# WirelessChargerTx.net
KiCad netlist of a schematic drawn in Altium Designer
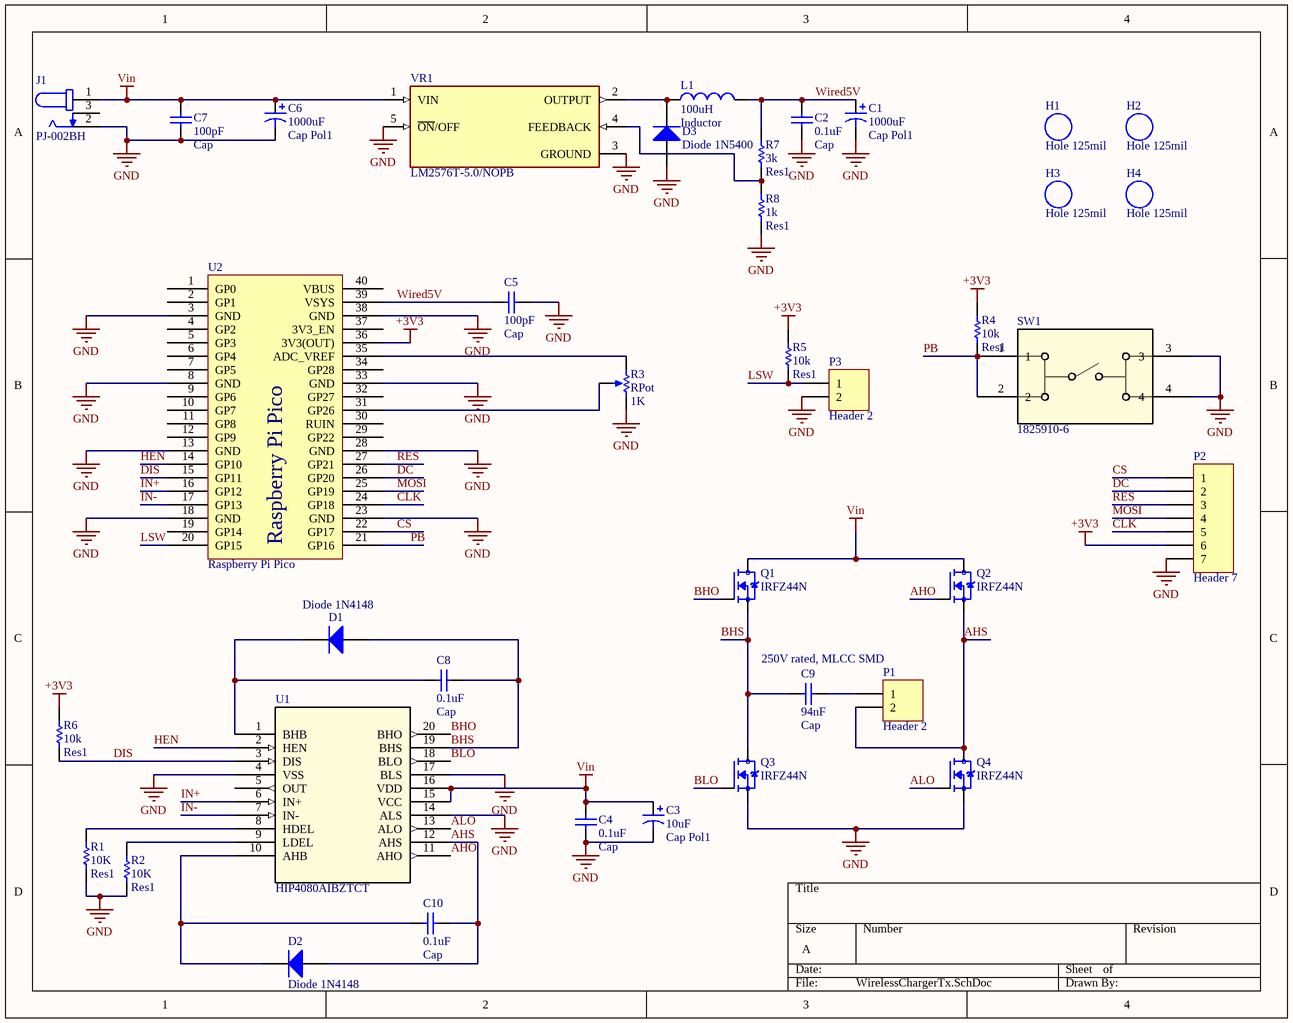
[diagram p0: WirelessChargerTx.SchDoc]

(export (version "E")
  (design (tool "Eeschema 10.0.6"))
  (components
    (comp (ref "C1")
      (value "Cap Pol1")
      (footprint "RB7.6-15")
      (description "Polarized Capacitor (Radial)")
      (fields (field (name "ALTIUM_VALUE") "1000uF") (field (name "PUBLISHER") "Altium Limited"))
      (libsource (lib "Miscellaneous Devices") (part "Cap Pol1"))
    )
    (comp (ref "C2")
      (value "Cap")
      (footprint "RAD-0.3")
      (description "Capacitor")
      (fields (field (name "ALTIUM_VALUE") "0.1uF") (field (name "PUBLISHER") "Altium Limited"))
      (libsource (lib "Miscellaneous Devices") (part "Cap"))
    )
    (comp (ref "C3")
      (value "Cap Pol1")
      (footprint "CAP_10uF")
      (description "Polarized Capacitor (Radial)")
      (fields (field (name "ALTIUM_VALUE") "10uF") (field (name "PUBLISHER") "Altium Limited"))
      (libsource (lib "Miscellaneous Devices") (part "Cap Pol1"))
    )
    (comp (ref "C4")
      (value "Cap")
      (footprint "c0805")
      (description "Capacitor")
      (fields (field (name "ALTIUM_VALUE") "0.1uF") (field (name "PUBLISHER") "Altium Limited"))
      (libsource (lib "Miscellaneous Devices") (part "Cap"))
    )
    (comp (ref "C5")
      (value "Cap")
      (footprint "RAD-0.3")
      (description "Capacitor")
      (fields (field (name "ALTIUM_VALUE") "100pF") (field (name "PUBLISHER") "Altium Limited"))
      (libsource (lib "Miscellaneous Devices") (part "Cap"))
    )
    (comp (ref "C6")
      (value "Cap Pol1")
      (footprint "RB7.6-15")
      (description "Polarized Capacitor (Radial)")
      (fields (field (name "ALTIUM_VALUE") "1000uF") (field (name "PUBLISHER") "Altium Limited"))
      (libsource (lib "Miscellaneous Devices") (part "Cap Pol1"))
    )
    (comp (ref "C7")
      (value "Cap")
      (footprint "RAD-0.3")
      (description "Capacitor")
      (fields (field (name "ALTIUM_VALUE") "100pF") (field (name "PUBLISHER") "Altium Limited"))
      (libsource (lib "Miscellaneous Devices") (part "Cap"))
    )
    (comp (ref "C8")
      (value "Cap")
      (footprint "C0805")
      (description "Capacitor")
      (fields (field (name "ALTIUM_VALUE") "0.1uF") (field (name "PUBLISHER") "Altium Limited"))
      (libsource (lib "Miscellaneous Devices") (part "Cap"))
    )
    (comp (ref "C9")
      (value "Cap")
      (footprint "C1210")
      (description "Capacitor")
      (fields (field (name "ALTIUM_VALUE") "94nF") (field (name "PUBLISHER") "Altium Limited"))
      (libsource (lib "Miscellaneous Devices") (part "Cap"))
    )
    (comp (ref "C10")
      (value "Cap")
      (footprint "C0805")
      (description "Capacitor")
      (fields (field (name "ALTIUM_VALUE") "0.1uF") (field (name "PUBLISHER") "Altium Limited"))
      (libsource (lib "Miscellaneous Devices") (part "Cap"))
    )
    (comp (ref "D1")
      (value "Diode 1N4148")
      (footprint "DO-35")
      (description "High Conductance Fast Diode")
      (fields (field (name "PUBLISHER") "Altium Limited"))
      (libsource (lib "Miscellaneous Devices") (part "Diode 1N4148"))
    )
    (comp (ref "D2")
      (value "Diode 1N4148")
      (footprint "DO-35")
      (description "High Conductance Fast Diode")
      (fields (field (name "PUBLISHER") "Altium Limited"))
      (libsource (lib "Miscellaneous Devices") (part "Diode 1N4148"))
    )
    (comp (ref "D3")
      (value "Diode 1N5400")
      (footprint "DO-201AD")
      (description "3 Amp General Purpose Rectifier")
      (fields (field (name "PUBLISHER") "Altium Limited"))
      (libsource (lib "Miscellaneous Devices") (part "Diode 1N5400"))
    )
    (comp (ref "H1")
      (value "Hole 125mil")
      (footprint "Hole 125mil")
      (libsource (lib "ECE Lib 22") (part "Hole 125mil"))
    )
    (comp (ref "H2")
      (value "Hole 125mil")
      (footprint "Hole 125mil")
      (libsource (lib "ECE Lib 22") (part "Hole 125mil"))
    )
    (comp (ref "H3")
      (value "Hole 125mil")
      (footprint "Hole 125mil")
      (libsource (lib "ECE Lib 22") (part "Hole 125mil"))
    )
    (comp (ref "H4")
      (value "Hole 125mil")
      (footprint "Hole 125mil")
      (libsource (lib "ECE Lib 22") (part "Hole 125mil"))
    )
    (comp (ref "J1")
      (value "PJ-002BH")
      (footprint "CUI_PJ-002BH")
      (description "2.5 x 6.5 mm, 5.0 A, Horizontal, Through Hole, Dc Power Jack Connector")
      (fields (field (name "MF") "Same Sky"))
      (libsource (lib "ERN") (part "PJ-002BH"))
    )
    (comp (ref "L1")
      (value "Inductor")
      (footprint "Inductor100uH")
      (fields (field (name "ALTIUM_VALUE") "100uH") (field (name "PUBLISHER") "Altium Limited"))
      (libsource (lib "Miscellaneous Devices") (part "Inductor"))
    )
    (comp (ref "P1")
      (value "Header 2")
      (footprint "HDR1X2")
      (description "Header, 2-Pin")
      (fields (field (name "PUBLISHER") "Altium Limited"))
      (libsource (lib "Miscellaneous Connectors") (part "Header 2"))
    )
    (comp (ref "P2")
      (value "Header 7")
      (footprint "HDR1X7")
      (description "Header, 7-Pin")
      (fields (field (name "PUBLISHER") "Altium Limited"))
      (libsource (lib "Miscellaneous Connectors") (part "Header 7"))
    )
    (comp (ref "P3")
      (value "Header 2")
      (footprint "HDR1X2")
      (description "Header, 2-Pin")
      (fields (field (name "PUBLISHER") "Altium Limited"))
      (libsource (lib "Miscellaneous Connectors") (part "Header 2"))
    )
    (comp (ref "Q1")
      (value "IRFZ44N")
      (footprint "TO254P1016X419X2286-3")
      (description "N-Channel 55 V 49A (Tc) 94W (Tc) Through Hole TO-220AB")
      (fields (field (name "MF") "Infineon Technologies"))
      (libsource (lib "ERN") (part "IRFZ44N"))
    )
    (comp (ref "Q2")
      (value "IRFZ44N")
      (footprint "TO254P1016X419X2286-3")
      (description "N-Channel 55 V 49A (Tc) 94W (Tc) Through Hole TO-220AB")
      (fields (field (name "MF") "Infineon Technologies"))
      (libsource (lib "ERN") (part "IRFZ44N"))
    )
    (comp (ref "Q3")
      (value "IRFZ44N")
      (footprint "TO254P1016X419X2286-3")
      (description "N-Channel 55 V 49A (Tc) 94W (Tc) Through Hole TO-220AB")
      (fields (field (name "MF") "Infineon Technologies"))
      (libsource (lib "ERN") (part "IRFZ44N"))
    )
    (comp (ref "Q4")
      (value "IRFZ44N")
      (footprint "TO254P1016X419X2286-3")
      (description "N-Channel 55 V 49A (Tc) 94W (Tc) Through Hole TO-220AB")
      (fields (field (name "MF") "Infineon Technologies"))
      (libsource (lib "ERN") (part "IRFZ44N"))
    )
    (comp (ref "R1")
      (value "Res1")
      (footprint "AXIAL-0.3")
      (description "Resistor")
      (fields (field (name "ALTIUM_VALUE") "10K") (field (name "PUBLISHER") "Altium Limited"))
      (libsource (lib "Miscellaneous Devices") (part "Res1"))
    )
    (comp (ref "R2")
      (value "Res1")
      (footprint "AXIAL-0.3")
      (description "Resistor")
      (fields (field (name "ALTIUM_VALUE") "10K") (field (name "PUBLISHER") "Altium Limited"))
      (libsource (lib "Miscellaneous Devices") (part "Res1"))
    )
    (comp (ref "R3")
      (value "RPot")
      (footprint "VR5")
      (description "Potentiometer")
      (fields (field (name "ALTIUM_VALUE") "1K") (field (name "PUBLISHER") "Altium Limited"))
      (libsource (lib "Miscellaneous Devices") (part "RPot"))
    )
    (comp (ref "R4")
      (value "Res1")
      (footprint "AXIAL-0.3")
      (description "Resistor")
      (fields (field (name "ALTIUM_VALUE") "10k") (field (name "PUBLISHER") "Altium Limited"))
      (libsource (lib "Miscellaneous Devices") (part "Res1"))
    )
    (comp (ref "R5")
      (value "Res1")
      (footprint "AXIAL-0.3")
      (description "Resistor")
      (fields (field (name "ALTIUM_VALUE") "10k") (field (name "PUBLISHER") "Altium Limited"))
      (libsource (lib "Miscellaneous Devices") (part "Res1"))
    )
    (comp (ref "R6")
      (value "Res1")
      (footprint "AXIAL-0.3")
      (description "Resistor")
      (fields (field (name "ALTIUM_VALUE") "10k") (field (name "PUBLISHER") "Altium Limited"))
      (libsource (lib "Miscellaneous Devices") (part "Res1"))
    )
    (comp (ref "R7")
      (value "Res1")
      (footprint "AXIAL-0.3")
      (description "Resistor")
      (fields (field (name "ALTIUM_VALUE") "3k") (field (name "PUBLISHER") "Altium Limited"))
      (libsource (lib "Miscellaneous Devices") (part "Res1"))
    )
    (comp (ref "R8")
      (value "Res1")
      (footprint "AXIAL-0.3")
      (description "Resistor")
      (fields (field (name "ALTIUM_VALUE") "1k") (field (name "PUBLISHER") "Altium Limited"))
      (libsource (lib "Miscellaneous Devices") (part "Res1"))
    )
    (comp (ref "SW1")
      (value "1825910-6")
      (footprint "SW4_1825910-B_TEC")
      (description "FSM4JH=6MM TACT SWITCH, HIGH TEMP")
      (fields (field (name "COPYRIGHT") "Copyright (C) 2026 Ultra Librarian. All rights reserved."))
      (libsource (lib "ERN") (part "1825910-6"))
    )
    (comp (ref "U1")
      (value "HIP4080AIBZTCT")
      (footprint "SOIC20_7P60X13_INR")
      (description "H Bridge Driver")
      (fields (field (name "COPYRIGHT") "Copyright (C) 2026 Ultra Librarian. All rights reserved."))
      (libsource (lib "ERN") (part "HIP4080AIBZTCT"))
    )
    (comp (ref "U2")
      (value "Raspberry Pi Pico")
      (footprint "Raspberry Pi Pico")
      (libsource (lib "ECE Lib 22") (part "Raspberry Pi Pico"))
    )
    (comp (ref "VR1")
      (value "LM2576T-5.0/NOPB")
      (footprint "T05A_TEX")
      (description "SIMPLE SWITCHERÂ® 40V, 3A Low Component Count Step-Down Regulator")
      (fields (field (name "MF") "Texas Instruments"))
      (libsource (lib "ERN") (part "LM2576T-5.0/NOPB"))
    )
  )
  (nets
    (net (code "1") (name "+3V3") (class "Default")
      (node (ref "P2") (pin "6") (pinfunction "6_6") (pintype "passive"))
      (node (ref "R4") (pin "2") (pinfunction "2_2") (pintype "passive"))
      (node (ref "R5") (pin "2") (pinfunction "2_2") (pintype "passive"))
      (node (ref "R6") (pin "2") (pinfunction "2_2") (pintype "passive"))
      (node (ref "U2") (pin "36") (pinfunction "3V3(OUT)_36") (pintype "passive"))
    )
    (net (code "2") (name "/AHO") (class "Default")
      (node (ref "Q2") (pin "1") (pinfunction "G_1") (pintype "passive"))
      (node (ref "U1") (pin "11") (pinfunction "AHO_11") (pintype "output"))
    )
    (net (code "3") (name "/AHS") (class "Default")
      (node (ref "C10") (pin "2") (pinfunction "2_2") (pintype "passive"))
      (node (ref "D2") (pin "1") (pinfunction "A_1") (pintype "passive"))
      (node (ref "P1") (pin "2") (pinfunction "2_2") (pintype "passive"))
      (node (ref "Q2") (pin "3") (pinfunction "S_3") (pintype "passive"))
      (node (ref "Q4") (pin "2") (pinfunction "D_2") (pintype "passive"))
      (node (ref "U1") (pin "12") (pinfunction "AHS_12") (pintype "passive"))
    )
    (net (code "4") (name "/ALO") (class "Default")
      (node (ref "Q4") (pin "1") (pinfunction "G_1") (pintype "passive"))
      (node (ref "U1") (pin "13") (pinfunction "ALO_13") (pintype "output"))
    )
    (net (code "5") (name "/BHO") (class "Default")
      (node (ref "Q1") (pin "1") (pinfunction "G_1") (pintype "passive"))
      (node (ref "U1") (pin "20") (pinfunction "BHO_20") (pintype "output"))
    )
    (net (code "6") (name "/BHS") (class "Default")
      (node (ref "C8") (pin "2") (pinfunction "2_2") (pintype "passive"))
      (node (ref "C9") (pin "1") (pinfunction "1_1") (pintype "passive"))
      (node (ref "D1") (pin "1") (pinfunction "A_1") (pintype "passive"))
      (node (ref "Q1") (pin "3") (pinfunction "S_3") (pintype "passive"))
      (node (ref "Q3") (pin "2") (pinfunction "D_2") (pintype "passive"))
      (node (ref "U1") (pin "19") (pinfunction "BHS_19") (pintype "passive"))
    )
    (net (code "7") (name "/BLO") (class "Default")
      (node (ref "Q3") (pin "1") (pinfunction "G_1") (pintype "passive"))
      (node (ref "U1") (pin "18") (pinfunction "BLO_18") (pintype "output"))
    )
    (net (code "8") (name "/CLK") (class "Default")
      (node (ref "P2") (pin "5") (pinfunction "5_5") (pintype "passive"))
      (node (ref "U2") (pin "24") (pinfunction "GP18_24") (pintype "passive"))
    )
    (net (code "9") (name "/CS") (class "Default")
      (node (ref "P2") (pin "1") (pinfunction "1_1") (pintype "passive"))
      (node (ref "U2") (pin "22") (pinfunction "GP17_22") (pintype "passive"))
    )
    (net (code "10") (name "/DC") (class "Default")
      (node (ref "P2") (pin "2") (pinfunction "2_2") (pintype "passive"))
      (node (ref "U2") (pin "26") (pinfunction "GP20_26") (pintype "passive"))
    )
    (net (code "11") (name "/DIS") (class "Default")
      (node (ref "R6") (pin "1") (pinfunction "1_1") (pintype "passive"))
      (node (ref "U1") (pin "3") (pinfunction "DIS_3") (pintype "input"))
      (node (ref "U2") (pin "15") (pinfunction "GP11_15") (pintype "passive"))
    )
    (net (code "12") (name "/HEN") (class "Default")
      (node (ref "U1") (pin "2") (pinfunction "HEN_2") (pintype "input"))
      (node (ref "U2") (pin "14") (pinfunction "GP10_14") (pintype "passive"))
    )
    (net (code "13") (name "/IN+") (class "Default")
      (node (ref "U1") (pin "6") (pinfunction "IN+_6") (pintype "input"))
      (node (ref "U2") (pin "16") (pinfunction "GP12_16") (pintype "passive"))
    )
    (net (code "14") (name "/IN-") (class "Default")
      (node (ref "U1") (pin "7") (pinfunction "IN-_7") (pintype "input"))
      (node (ref "U2") (pin "17") (pinfunction "GP13_17") (pintype "passive"))
    )
    (net (code "15") (name "/LSW") (class "Default")
      (node (ref "P3") (pin "1") (pinfunction "1_1") (pintype "passive"))
      (node (ref "R5") (pin "1") (pinfunction "1_1") (pintype "passive"))
      (node (ref "U2") (pin "20") (pinfunction "GP15_20") (pintype "passive"))
    )
    (net (code "16") (name "/MOSI") (class "Default")
      (node (ref "P2") (pin "4") (pinfunction "4_4") (pintype "passive"))
      (node (ref "U2") (pin "25") (pinfunction "GP19_25") (pintype "passive"))
    )
    (net (code "17") (name "/PB") (class "Default")
      (node (ref "R4") (pin "1") (pinfunction "1_1") (pintype "passive"))
      (node (ref "SW1") (pin "1") (pinfunction "1_1") (pintype "passive"))
      (node (ref "SW1") (pin "2") (pinfunction "2_2") (pintype "passive"))
      (node (ref "U2") (pin "21") (pinfunction "GP16_21") (pintype "passive"))
    )
    (net (code "18") (name "/RES") (class "Default")
      (node (ref "P2") (pin "3") (pinfunction "3_3") (pintype "passive"))
      (node (ref "U2") (pin "27") (pinfunction "GP21_27") (pintype "passive"))
    )
    (net (code "19") (name "/Wired5V") (class "Default")
      (node (ref "C1") (pin "1") (pinfunction "1_1") (pintype "passive"))
      (node (ref "C2") (pin "2") (pinfunction "2_2") (pintype "passive"))
      (node (ref "C5") (pin "1") (pinfunction "1_1") (pintype "passive"))
      (node (ref "L1") (pin "2") (pinfunction "2_2") (pintype "passive"))
      (node (ref "R7") (pin "2") (pinfunction "2_2") (pintype "passive"))
      (node (ref "U2") (pin "39") (pinfunction "VSYS_39") (pintype "passive"))
    )
    (net (code "20") (name "GND") (class "Default")
      (node (ref "C1") (pin "2") (pinfunction "2_2") (pintype "passive"))
      (node (ref "C2") (pin "1") (pinfunction "1_1") (pintype "passive"))
      (node (ref "C3") (pin "2") (pinfunction "2_2") (pintype "passive"))
      (node (ref "C4") (pin "1") (pinfunction "1_1") (pintype "passive"))
      (node (ref "C5") (pin "2") (pinfunction "2_2") (pintype "passive"))
      (node (ref "C6") (pin "2") (pinfunction "2_2") (pintype "passive"))
      (node (ref "C7") (pin "2") (pinfunction "2_2") (pintype "passive"))
      (node (ref "D3") (pin "1") (pinfunction "A_1") (pintype "passive"))
      (node (ref "J1") (pin "2") (pinfunction "2_2") (pintype "passive"))
      (node (ref "P2") (pin "7") (pinfunction "7_7") (pintype "passive"))
      (node (ref "P3") (pin "2") (pinfunction "2_2") (pintype "passive"))
      (node (ref "Q3") (pin "3") (pinfunction "S_3") (pintype "passive"))
      (node (ref "Q4") (pin "3") (pinfunction "S_3") (pintype "passive"))
      (node (ref "R1") (pin "1") (pinfunction "1_1") (pintype "passive"))
      (node (ref "R2") (pin "1") (pinfunction "1_1") (pintype "passive"))
      (node (ref "R3") (pin "2") (pinfunction "BOT_2") (pintype "passive"))
      (node (ref "R8") (pin "1") (pinfunction "1_1") (pintype "passive"))
      (node (ref "SW1") (pin "3") (pinfunction "3_3") (pintype "passive"))
      (node (ref "SW1") (pin "4") (pinfunction "4_4") (pintype "passive"))
      (node (ref "U1") (pin "14") (pinfunction "ALS_14") (pintype "passive"))
      (node (ref "U1") (pin "17") (pinfunction "BLS_17") (pintype "passive"))
      (node (ref "U1") (pin "4") (pinfunction "VSS_4") (pintype "power_in"))
      (node (ref "U2") (pin "13") (pinfunction "GND_13") (pintype "passive"))
      (node (ref "U2") (pin "18") (pinfunction "GND_18") (pintype "passive"))
      (node (ref "U2") (pin "23") (pinfunction "GND_23") (pintype "passive"))
      (node (ref "U2") (pin "28") (pinfunction "GND_28") (pintype "passive"))
      (node (ref "U2") (pin "3") (pinfunction "GND_3") (pintype "passive"))
      (node (ref "U2") (pin "33") (pinfunction "GND_33") (pintype "passive"))
      (node (ref "U2") (pin "38") (pinfunction "GND_38") (pintype "passive"))
      (node (ref "U2") (pin "8") (pinfunction "GND_8") (pintype "passive"))
      (node (ref "VR1") (pin "3") (pinfunction "GROUND_3") (pintype "power_in"))
      (node (ref "VR1") (pin "5") (pinfunction "~{ON}/OFF_5") (pintype "input"))
    )
    (net (code "21") (name "Net-(C9-Pad2)") (class "Default")
      (node (ref "C9") (pin "2") (pinfunction "2_2") (pintype "passive"))
      (node (ref "P1") (pin "1") (pinfunction "1_1") (pintype "passive"))
    )
    (net (code "22") (name "Net-(D1-K)") (class "Default")
      (node (ref "C8") (pin "1") (pinfunction "1_1") (pintype "passive"))
      (node (ref "D1") (pin "2") (pinfunction "K_2") (pintype "passive"))
      (node (ref "U1") (pin "1") (pinfunction "BHB_1") (pintype "passive"))
    )
    (net (code "23") (name "Net-(D2-K)") (class "Default")
      (node (ref "C10") (pin "1") (pinfunction "1_1") (pintype "passive"))
      (node (ref "D2") (pin "2") (pinfunction "K_2") (pintype "passive"))
      (node (ref "U1") (pin "10") (pinfunction "AHB_10") (pintype "passive"))
    )
    (net (code "24") (name "Net-(D3-K)") (class "Default")
      (node (ref "D3") (pin "2") (pinfunction "K_2") (pintype "passive"))
      (node (ref "L1") (pin "1") (pinfunction "1_1") (pintype "passive"))
      (node (ref "VR1") (pin "2") (pinfunction "OUTPUT_2") (pintype "output"))
    )
    (net (code "25") (name "Net-(R3-TAP)") (class "Default")
      (node (ref "R3") (pin "3") (pinfunction "TAP_3") (pintype "passive"))
      (node (ref "U2") (pin "31") (pinfunction "GP26_31") (pintype "passive"))
    )
    (net (code "26") (name "Net-(R3-TOP)") (class "Default")
      (node (ref "R3") (pin "1") (pinfunction "TOP_1") (pintype "passive"))
      (node (ref "U2") (pin "35") (pinfunction "ADC_VREF_35") (pintype "passive"))
    )
    (net (code "27") (name "Net-(U1-HDEL)") (class "Default")
      (node (ref "R1") (pin "2") (pinfunction "2_2") (pintype "passive"))
      (node (ref "U1") (pin "8") (pinfunction "HDEL_8") (pintype "passive"))
    )
    (net (code "28") (name "Net-(U1-LDEL)") (class "Default")
      (node (ref "R2") (pin "2") (pinfunction "2_2") (pintype "passive"))
      (node (ref "U1") (pin "9") (pinfunction "LDEL_9") (pintype "passive"))
    )
    (net (code "29") (name "Net-(VR1-FEEDBACK)") (class "Default")
      (node (ref "R7") (pin "1") (pinfunction "1_1") (pintype "passive"))
      (node (ref "R8") (pin "2") (pinfunction "2_2") (pintype "passive"))
      (node (ref "VR1") (pin "4") (pinfunction "FEEDBACK_4") (pintype "input"))
    )
    (net (code "30") (name "Vin") (class "Default")
      (node (ref "C3") (pin "1") (pinfunction "1_1") (pintype "passive"))
      (node (ref "C4") (pin "2") (pinfunction "2_2") (pintype "passive"))
      (node (ref "C6") (pin "1") (pinfunction "1_1") (pintype "passive"))
      (node (ref "C7") (pin "1") (pinfunction "1_1") (pintype "passive"))
      (node (ref "J1") (pin "1") (pinfunction "1_1") (pintype "passive"))
      (node (ref "Q1") (pin "2") (pinfunction "D_2") (pintype "passive"))
      (node (ref "Q2") (pin "2") (pinfunction "D_2") (pintype "passive"))
      (node (ref "U1") (pin "15") (pinfunction "VCC_15") (pintype "power_in"))
      (node (ref "U1") (pin "16") (pinfunction "VDD_16") (pintype "power_in"))
      (node (ref "VR1") (pin "1") (pinfunction "VIN_1") (pintype "input"))
    )
    (net (code "31") (name "unconnected-(J1-Pad3)") (class "Default")
      (node (ref "J1") (pin "3") (pinfunction "3_3") (pintype "passive"))
    )
    (net (code "32") (name "unconnected-(U1-OUT-Pad5)") (class "Default")
      (node (ref "U1") (pin "5") (pinfunction "OUT_5") (pintype "output"))
    )
    (net (code "33") (name "unconnected-(U2-3V3_EN-Pad37)") (class "Default")
      (node (ref "U2") (pin "37") (pinfunction "3V3_EN_37") (pintype "passive"))
    )
    (net (code "34") (name "unconnected-(U2-GP0-Pad1)") (class "Default")
      (node (ref "U2") (pin "1") (pinfunction "GP0_1") (pintype "passive"))
    )
    (net (code "35") (name "unconnected-(U2-GP1-Pad2)") (class "Default")
      (node (ref "U2") (pin "2") (pinfunction "GP1_2") (pintype "passive"))
    )
    (net (code "36") (name "unconnected-(U2-GP2-Pad4)") (class "Default")
      (node (ref "U2") (pin "4") (pinfunction "GP2_4") (pintype "passive"))
    )
    (net (code "37") (name "unconnected-(U2-GP3-Pad5)") (class "Default")
      (node (ref "U2") (pin "5") (pinfunction "GP3_5") (pintype "passive"))
    )
    (net (code "38") (name "unconnected-(U2-GP4-Pad6)") (class "Default")
      (node (ref "U2") (pin "6") (pinfunction "GP4_6") (pintype "passive"))
    )
    (net (code "39") (name "unconnected-(U2-GP5-Pad7)") (class "Default")
      (node (ref "U2") (pin "7") (pinfunction "GP5_7") (pintype "passive"))
    )
    (net (code "40") (name "unconnected-(U2-GP6-Pad9)") (class "Default")
      (node (ref "U2") (pin "9") (pinfunction "GP6_9") (pintype "passive"))
    )
    (net (code "41") (name "unconnected-(U2-GP7-Pad10)") (class "Default")
      (node (ref "U2") (pin "10") (pinfunction "GP7_10") (pintype "passive"))
    )
    (net (code "42") (name "unconnected-(U2-GP8-Pad11)") (class "Default")
      (node (ref "U2") (pin "11") (pinfunction "GP8_11") (pintype "passive"))
    )
    (net (code "43") (name "unconnected-(U2-GP9-Pad12)") (class "Default")
      (node (ref "U2") (pin "12") (pinfunction "GP9_12") (pintype "passive"))
    )
    (net (code "44") (name "unconnected-(U2-GP14-Pad19)") (class "Default")
      (node (ref "U2") (pin "19") (pinfunction "GP14_19") (pintype "passive"))
    )
    (net (code "45") (name "unconnected-(U2-GP22-Pad29)") (class "Default")
      (node (ref "U2") (pin "29") (pinfunction "GP22_29") (pintype "passive"))
    )
    (net (code "46") (name "unconnected-(U2-GP27-Pad32)") (class "Default")
      (node (ref "U2") (pin "32") (pinfunction "GP27_32") (pintype "passive"))
    )
    (net (code "47") (name "unconnected-(U2-GP28-Pad34)") (class "Default")
      (node (ref "U2") (pin "34") (pinfunction "GP28_34") (pintype "passive"))
    )
    (net (code "48") (name "unconnected-(U2-RUIN-Pad30)") (class "Default")
      (node (ref "U2") (pin "30") (pinfunction "RUIN_30") (pintype "passive"))
    )
    (net (code "49") (name "unconnected-(U2-VBUS-Pad40)") (class "Default")
      (node (ref "U2") (pin "40") (pinfunction "VBUS_40") (pintype "passive"))
    )
  )
)
